# mapleCUx_large_400-012.net
KiCad netlist of a schematic drawn in EAGLE
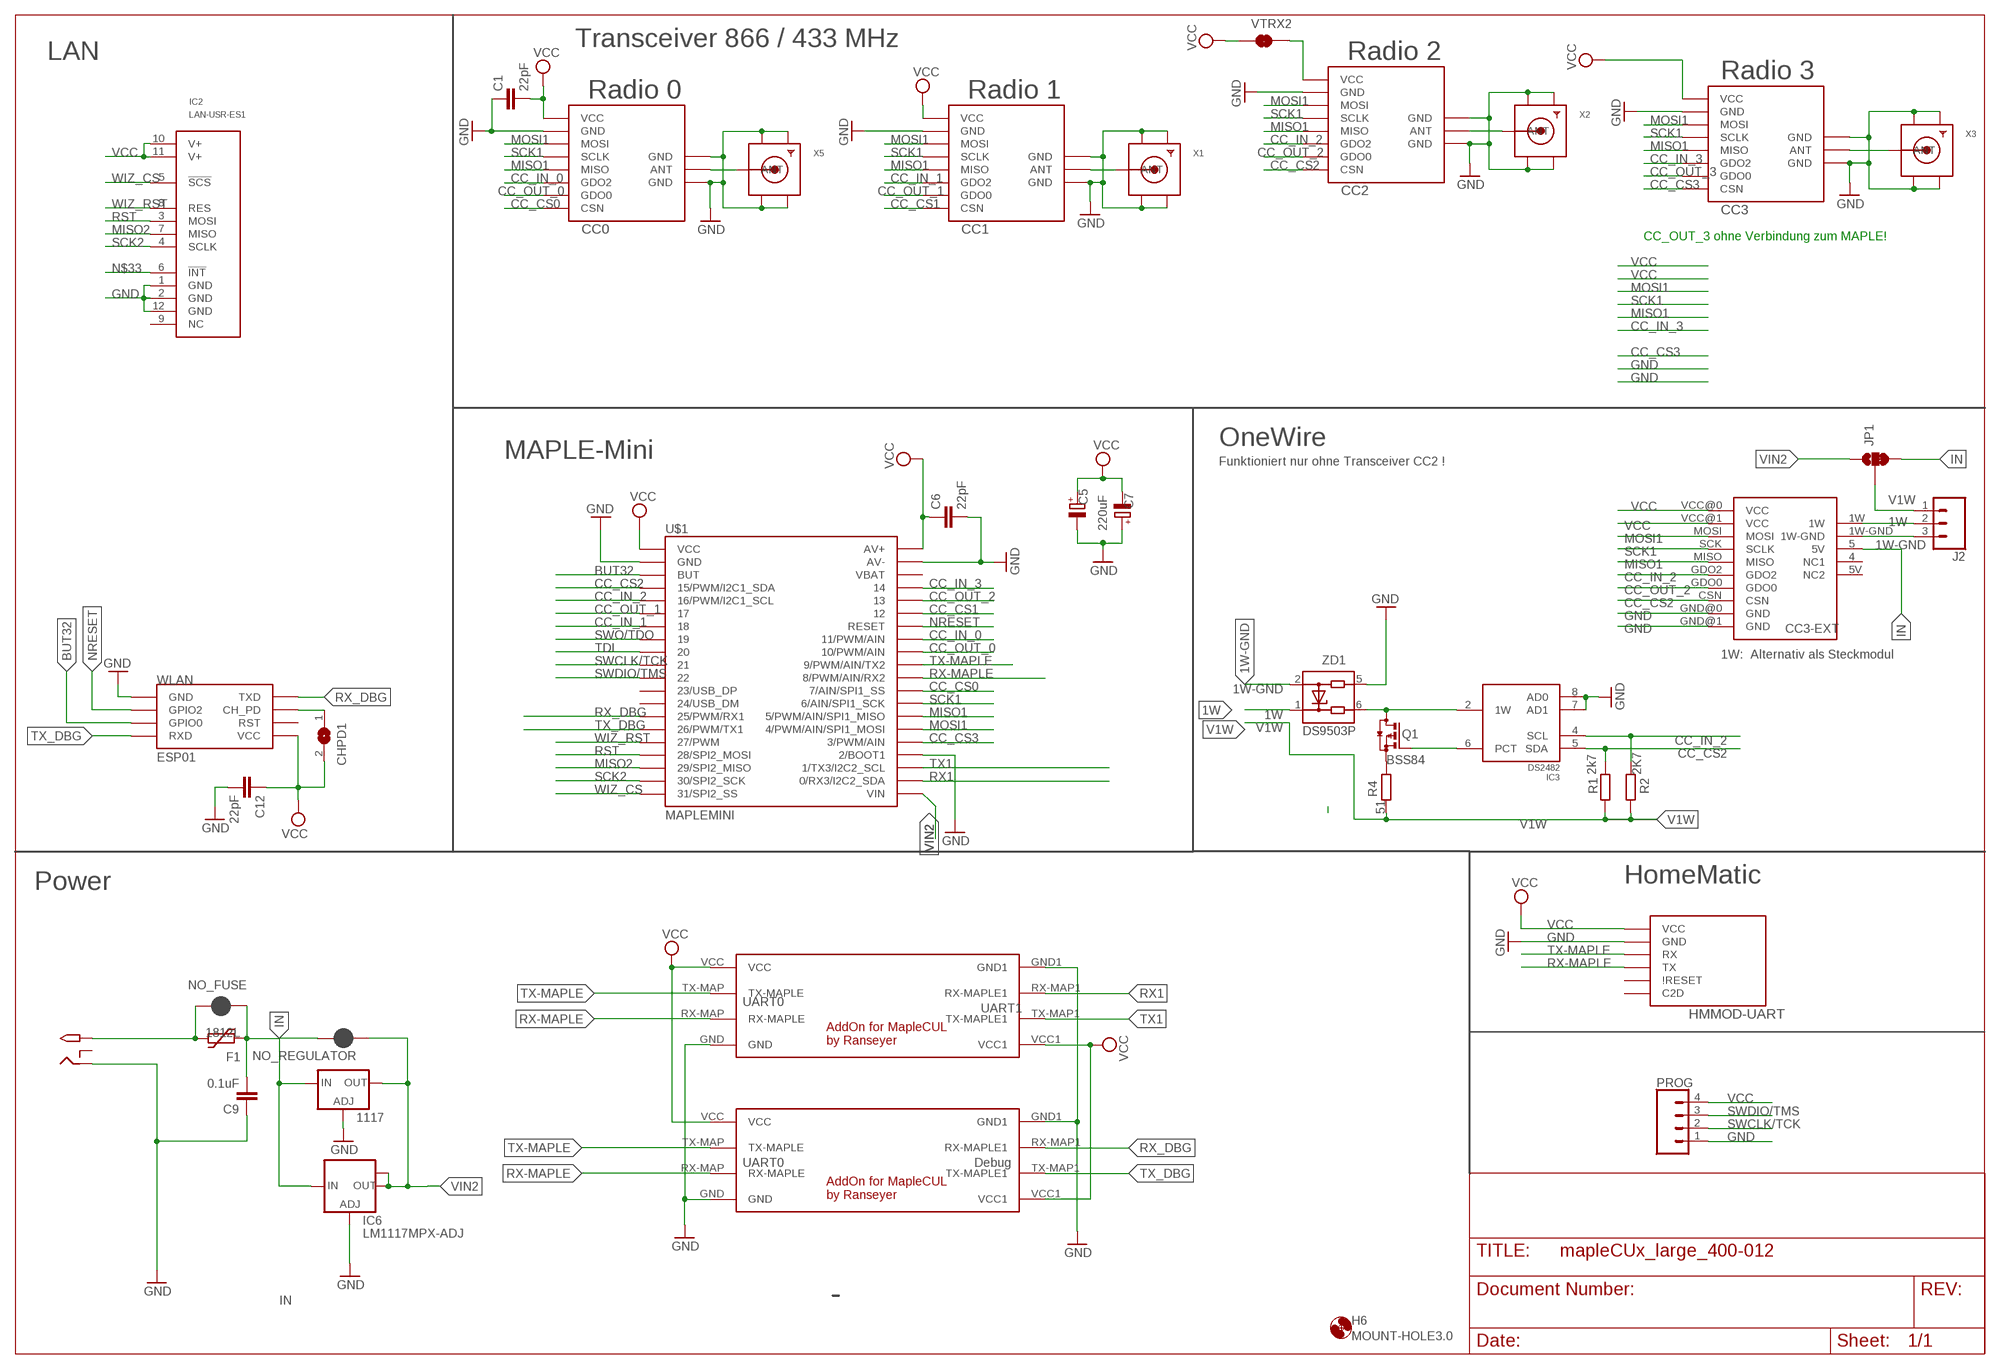
[diagram p0: schematic, sheet 1]

(export (version "E")
  (design (tool "Eeschema 10.0.6"))
  (components
    (comp (ref "1117")
      (value "LD117ADT50TR")
      (footprint "eagle-import:DPACK")
      (libsource (lib "eagle-import") (part "LD117A?DT50TR"))
    )
    (comp (ref "C1")
      (value "22pF")
      (footprint "eagle-import:C0805")
      (libsource (lib "eagle-import") (part "C-EUC0805"))
    )
    (comp (ref "C5")
      (value "220uF")
      (footprint "eagle-import:E5-8,5")
      (libsource (lib "eagle-import") (part "CPOL-EUE5-8.5"))
    )
    (comp (ref "C6")
      (value "22pF")
      (footprint "eagle-import:C0805")
      (libsource (lib "eagle-import") (part "C-EUC0805"))
    )
    (comp (ref "C7")
      (value "CPOL-EUSMCE")
      (footprint "eagle-import:SMC_E")
      (libsource (lib "eagle-import") (part "rcl_334_CPOL-EUSMCE"))
    )
    (comp (ref "C9")
      (value "0.1uF")
      (footprint "eagle-import:C1206")
      (libsource (lib "eagle-import") (part "C-EUC1206"))
    )
    (comp (ref "C12")
      (value "22pF")
      (footprint "eagle-import:C0805")
      (libsource (lib "eagle-import") (part "C-EUC0805"))
    )
    (comp (ref "CC0")
      (value "CC1101")
      (footprint "eagle-import:CC1101_MODULE1_SMD")
      (libsource (lib "eagle-import") (part "CC1101_MODULE1SMD"))
    )
    (comp (ref "CC1")
      (value "CC1101_MODULE1SMD")
      (footprint "eagle-import:CC1101_MODULE1_SMD")
      (libsource (lib "eagle-import") (part "CC1101_MODULE1SMD"))
    )
    (comp (ref "CC2")
      (value "CC1101_MODULE1SMD")
      (footprint "eagle-import:CC1101_MODULE1_SMD")
      (libsource (lib "eagle-import") (part "CC1101_MODULE1SMD"))
    )
    (comp (ref "CC3")
      (value "CC1101_MODULE1SMD")
      (footprint "eagle-import:CC1101_MODULE1_SMD")
      (libsource (lib "eagle-import") (part "CC1101_MODULE1SMD"))
    )
    (comp (ref "CC3-EXT")
      (value "ONEWIRE-MODULE")
      (footprint "eagle-import:ONEWIRE_CC1101_MODULE3_DIL")
      (libsource (lib "eagle-import") (part "ONEWIRE-MODULE"))
    )
    (comp (ref "CHPD1")
      (value "SJ")
      (footprint "eagle-import:SJ")
      (libsource (lib "eagle-import") (part "SJ"))
    )
    (comp (ref "F1")
      (value "1812L")
      (footprint "eagle-import:1812L")
      (libsource (lib "eagle-import") (part "1812L"))
    )
    (comp (ref "H6")
      (value "MOUNT-HOLE3.0")
      (footprint "eagle-import:3,0")
      (libsource (lib "eagle-import") (part "MOUNT-HOLE3.0"))
    )
    (comp (ref "HMMOD-UART")
      (value "HM-MOD-UARTDIL")
      (footprint "eagle-import:HM-MOD-UART-DIL")
      (libsource (lib "eagle-import") (part "HM-MOD-UARTDIL"))
    )
    (comp (ref "IC2")
      (value "LAN-USR-ES1")
      (footprint "eagle-import:USR-ES1")
      (libsource (lib "eagle-import") (part "LAN-USR-ES1"))
    )
    (comp (ref "IC3")
      (value "DS2482")
      (footprint "eagle-import:SO08")
      (libsource (lib "eagle-import") (part "DS2482-100S"))
    )
    (comp (ref "IC6")
      (value "LM1117MPX-ADJ")
      (footprint "eagle-import:SOT223")
      (libsource (lib "eagle-import") (part "LM1117MPX-ADJ"))
    )
    (comp (ref "J2")
      (value "CONN_03LONGPADS")
      (footprint "eagle-import:1X03_LONGPADS")
      (libsource (lib "eagle-import") (part "CONN_03LONGPADS"))
    )
    (comp (ref "JP1")
      (value "JUMPER-SMT_3_1-NC_TRACE_SILK")
      (footprint "eagle-import:SMT-JUMPER_3_1-NC_TRACE_SILK")
      (libsource (lib "eagle-import") (part "JUMPER-SMT_3_1-NC_TRACE_SILK"))
    )
    (comp (ref "NO_FUSE")
      (value "JUMPER-SMT_2_NC_PASTE_NO-SILK")
      (footprint "eagle-import:SMT-JUMPER_2_NC_PASTE_NO-SILK")
      (libsource (lib "eagle-import") (part "JUMPER-SMT_2_NC_PASTE_NO-SILK"))
    )
    (comp (ref "NO_REGULATOR")
      (value "JUMPER-SMT_2_NC_PASTE_NO-SILK")
      (footprint "eagle-import:SMT-JUMPER_2_NC_PASTE_NO-SILK")
      (libsource (lib "eagle-import") (part "JUMPER-SMT_2_NC_PASTE_NO-SILK"))
    )
    (comp (ref "PROG")
      (value "CONN_04LOCK")
      (footprint "eagle-import:1X04_LOCK")
      (libsource (lib "eagle-import") (part "CONN_04LOCK"))
    )
    (comp (ref "Q1")
      (value "BSS84")
      (footprint "eagle-import:SOT23")
      (libsource (lib "eagle-import") (part "BSS84"))
    )
    (comp (ref "R1")
      (value "2k7")
      (footprint "eagle-import:R0805")
      (libsource (lib "eagle-import") (part "R-EU_R0805"))
    )
    (comp (ref "R2")
      (value "2K7")
      (footprint "eagle-import:R0805")
      (libsource (lib "eagle-import") (part "R-EU_R0805"))
    )
    (comp (ref "R4")
      (value "51")
      (footprint "eagle-import:R0805")
      (libsource (lib "eagle-import") (part "R-EU_R0805"))
    )
    (comp (ref "U$1")
      (value "MAPLEMINI")
      (footprint "eagle-import:20-DIP")
      (libsource (lib "eagle-import") (part "MAPLEMINI"))
    )
    (comp (ref "U$2")
      (value "2.1MMJACKTHM")
      (footprint "eagle-import:PJ-102A")
      (libsource (lib "eagle-import") (part "2.1MMJACKTHM"))
    )
    (comp (ref "U$3")
      (value "MAPLE-CUL-ADDON-V01")
      (footprint "eagle-import:MAPLE-CUL-V01")
      (libsource (lib "eagle-import") (part "MAPLE-CUL-ADDON-V01"))
    )
    (comp (ref "U$4")
      (value "MAPLE-CUL-ADDON-V01")
      (footprint "eagle-import:MAPLE-CUL-V01")
      (libsource (lib "eagle-import") (part "MAPLE-CUL-ADDON-V01"))
    )
    (comp (ref "VTRX2")
      (value "JUMPER-SMT_2_NC_TRACE_SILK")
      (footprint "eagle-import:SMT-JUMPER_2_NC_TRACE_SILK")
      (libsource (lib "eagle-import") (part "JUMPER-SMT_2_NC_TRACE_SILK"))
    )
    (comp (ref "WLAN")
      (value "ESP01")
      (footprint "eagle-import:ESP01")
      (libsource (lib "eagle-import") (part "ESP01"))
    )
    (comp (ref "X1")
      (value "SMACONNECTOR_EDGE")
      (footprint "eagle-import:SMA_EDGELAUNCH")
      (libsource (lib "eagle-import") (part "SMACONNECTOR_EDGE"))
    )
    (comp (ref "X2")
      (value "SMACONNECTOR_EDGE")
      (footprint "eagle-import:SMA_EDGELAUNCH")
      (libsource (lib "eagle-import") (part "SMACONNECTOR_EDGE"))
    )
    (comp (ref "X3")
      (value "SMACONNECTOR_EDGE")
      (footprint "eagle-import:SMA_EDGELAUNCH")
      (libsource (lib "eagle-import") (part "SMACONNECTOR_EDGE"))
    )
    (comp (ref "X5")
      (value "SMACONNECTOR_EDGE")
      (footprint "eagle-import:SMA_EDGELAUNCH")
      (libsource (lib "eagle-import") (part "SMACONNECTOR_EDGE"))
    )
    (comp (ref "ZD1")
      (value "DS9503P")
      (footprint "eagle-import:TSOC6")
      (libsource (lib "eagle-import") (part "DS9503P"))
    )
  )
  (nets
    (net (code "1") (name "/CC_CS0") (class "Default")
      (node (ref "CC0") (pin "CSN") (pinfunction "CSN_CSN") (pintype "bidirectional"))
      (node (ref "U$1") (pin "29") (pinfunction "7/AIN/SPI1_SS_29") (pintype "bidirectional"))
    )
    (net (code "2") (name "/CC_CS1") (class "Default")
      (node (ref "CC1") (pin "CSN") (pinfunction "CSN_CSN") (pintype "bidirectional"))
      (node (ref "U$1") (pin "35") (pinfunction "12_35") (pintype "bidirectional"))
    )
    (net (code "3") (name "/CC_CS2") (class "Default")
      (node (ref "CC2") (pin "CSN") (pinfunction "CSN_CSN") (pintype "bidirectional"))
      (node (ref "CC3-EXT") (pin "CSN") (pinfunction "CSN_CSN") (pintype "bidirectional"))
      (node (ref "IC3") (pin "5") (pinfunction "SDA_5") (pintype "bidirectional"))
      (node (ref "R1") (pin "2") (pinfunction "2_2") (pintype "passive"))
      (node (ref "U$1") (pin "4") (pinfunction "15/PWM/I2C1_SDA_4") (pintype "bidirectional"))
    )
    (net (code "4") (name "/CC_CS3") (class "Default")
      (node (ref "CC3") (pin "CSN") (pinfunction "CSN_CSN") (pintype "bidirectional"))
      (node (ref "U$1") (pin "25") (pinfunction "3/PWM/AIN_25") (pintype "bidirectional"))
    )
    (net (code "5") (name "/CC_IN_0") (class "Default")
      (node (ref "CC0") (pin "GDO2") (pinfunction "GDO2_GDO2") (pintype "bidirectional"))
      (node (ref "U$1") (pin "33") (pinfunction "11/PWM/AIN_33") (pintype "bidirectional"))
    )
    (net (code "6") (name "/CC_IN_1") (class "Default")
      (node (ref "CC1") (pin "GDO2") (pinfunction "GDO2_GDO2") (pintype "bidirectional"))
      (node (ref "U$1") (pin "7") (pinfunction "18_7") (pintype "bidirectional"))
    )
    (net (code "7") (name "/CC_IN_2") (class "Default")
      (node (ref "CC2") (pin "GDO2") (pinfunction "GDO2_GDO2") (pintype "bidirectional"))
      (node (ref "CC3-EXT") (pin "GDO2") (pinfunction "GDO2_GDO2") (pintype "bidirectional"))
      (node (ref "IC3") (pin "4") (pinfunction "SCL_4") (pintype "input"))
      (node (ref "R2") (pin "2") (pinfunction "2_2") (pintype "passive"))
      (node (ref "U$1") (pin "5") (pinfunction "16/PWM/I2C1_SCL_5") (pintype "bidirectional"))
    )
    (net (code "8") (name "/CC_IN_3") (class "Default")
      (node (ref "CC3") (pin "GDO2") (pinfunction "GDO2_GDO2") (pintype "bidirectional"))
      (node (ref "U$1") (pin "37") (pinfunction "14_37") (pintype "bidirectional"))
    )
    (net (code "9") (name "/CC_OUT_0") (class "Default")
      (node (ref "CC0") (pin "GDO0") (pinfunction "GDO0_GDO0") (pintype "bidirectional"))
      (node (ref "U$1") (pin "32") (pinfunction "10/PWM/AIN_32") (pintype "bidirectional"))
    )
    (net (code "10") (name "/CC_OUT_1") (class "Default")
      (node (ref "CC1") (pin "GDO0") (pinfunction "GDO0_GDO0") (pintype "bidirectional"))
      (node (ref "U$1") (pin "6") (pinfunction "17_6") (pintype "bidirectional"))
    )
    (net (code "11") (name "/CC_OUT_2") (class "Default")
      (node (ref "CC2") (pin "GDO0") (pinfunction "GDO0_GDO0") (pintype "bidirectional"))
      (node (ref "CC3-EXT") (pin "GDO0") (pinfunction "GDO0_GDO0") (pintype "bidirectional"))
      (node (ref "U$1") (pin "36") (pinfunction "13_36") (pintype "bidirectional"))
    )
    (net (code "12") (name "/CC_OUT_3") (class "Default")
      (node (ref "CC3") (pin "GDO0") (pinfunction "GDO0_GDO0") (pintype "bidirectional"))
    )
    (net (code "13") (name "/MISO1") (class "Default")
      (node (ref "CC0") (pin "MISO") (pinfunction "MISO_MISO") (pintype "bidirectional"))
      (node (ref "CC1") (pin "MISO") (pinfunction "MISO_MISO") (pintype "bidirectional"))
      (node (ref "CC2") (pin "MISO") (pinfunction "MISO_MISO") (pintype "bidirectional"))
      (node (ref "CC3") (pin "MISO") (pinfunction "MISO_MISO") (pintype "bidirectional"))
      (node (ref "CC3-EXT") (pin "MISO") (pinfunction "MISO_MISO") (pintype "bidirectional"))
      (node (ref "U$1") (pin "27") (pinfunction "5/PWM/AIN/SPI1_MISO_27") (pintype "bidirectional"))
    )
    (net (code "14") (name "/MISO2") (class "Default")
      (node (ref "IC2") (pin "7") (pinfunction "MISO_7") (pintype "bidirectional"))
      (node (ref "U$1") (pin "18") (pinfunction "29/SPI2_MISO_18") (pintype "bidirectional"))
    )
    (net (code "15") (name "/MOSI1") (class "Default")
      (node (ref "CC0") (pin "MOSI") (pinfunction "MOSI_MOSI") (pintype "bidirectional"))
      (node (ref "CC1") (pin "MOSI") (pinfunction "MOSI_MOSI") (pintype "bidirectional"))
      (node (ref "CC2") (pin "MOSI") (pinfunction "MOSI_MOSI") (pintype "bidirectional"))
      (node (ref "CC3") (pin "MOSI") (pinfunction "MOSI_MOSI") (pintype "bidirectional"))
      (node (ref "CC3-EXT") (pin "MOSI") (pinfunction "MOSI_MOSI") (pintype "bidirectional"))
      (node (ref "U$1") (pin "26") (pinfunction "4/PWM/AIN/SPI1_MOSI_26") (pintype "bidirectional"))
    )
    (net (code "16") (name "/N$33") (class "Default")
      (node (ref "IC2") (pin "6") (pinfunction "~{INT}_6") (pintype "output"))
    )
    (net (code "17") (name "/RST") (class "Default")
      (node (ref "IC2") (pin "3") (pinfunction "MOSI_3") (pintype "bidirectional"))
      (node (ref "U$1") (pin "17") (pinfunction "28/SPI2_MOSI_17") (pintype "bidirectional"))
    )
    (net (code "18") (name "/SCK1") (class "Default")
      (node (ref "CC0") (pin "SCLK") (pinfunction "SCLK_SCLK") (pintype "bidirectional"))
      (node (ref "CC1") (pin "SCLK") (pinfunction "SCLK_SCLK") (pintype "bidirectional"))
      (node (ref "CC2") (pin "SCLK") (pinfunction "SCLK_SCLK") (pintype "bidirectional"))
      (node (ref "CC3") (pin "SCLK") (pinfunction "SCLK_SCLK") (pintype "bidirectional"))
      (node (ref "CC3-EXT") (pin "SCK") (pinfunction "SCLK_SCK") (pintype "bidirectional"))
      (node (ref "U$1") (pin "28") (pinfunction "6/AIN/SPI1_SCK_28") (pintype "bidirectional"))
    )
    (net (code "19") (name "/SCK2") (class "Default")
      (node (ref "IC2") (pin "4") (pinfunction "SCLK_4") (pintype "input"))
      (node (ref "U$1") (pin "19") (pinfunction "30/SPI2_SCK_19") (pintype "bidirectional"))
    )
    (net (code "20") (name "/SWCLK{slash}TCK") (class "Default")
      (node (ref "PROG") (pin "2") (pinfunction "2_2") (pintype "passive"))
      (node (ref "U$1") (pin "10") (pinfunction "21_10") (pintype "bidirectional"))
    )
    (net (code "21") (name "/SWDIO{slash}TMS") (class "Default")
      (node (ref "PROG") (pin "3") (pinfunction "3_3") (pintype "passive"))
      (node (ref "U$1") (pin "11") (pinfunction "22_11") (pintype "bidirectional"))
    )
    (net (code "22") (name "/SWO{slash}TDO") (class "Default")
      (node (ref "U$1") (pin "8") (pinfunction "19_8") (pintype "bidirectional"))
    )
    (net (code "23") (name "/TDI") (class "Default")
      (node (ref "U$1") (pin "9") (pinfunction "20_9") (pintype "bidirectional"))
    )
    (net (code "24") (name "/WIZ_CS") (class "Default")
      (node (ref "IC2") (pin "5") (pinfunction "~{SCS}_5") (pintype "input"))
      (node (ref "U$1") (pin "20") (pinfunction "31/SPI2_SS_20") (pintype "bidirectional"))
    )
    (net (code "25") (name "/WIZ_RST") (class "Default")
      (node (ref "IC2") (pin "8") (pinfunction "RES_8") (pintype "input"))
      (node (ref "U$1") (pin "16") (pinfunction "27/PWM_16") (pintype "bidirectional"))
    )
    (net (code "26") (name "1W") (class "Default")
      (node (ref "CC3-EXT") (pin "1W") (pinfunction "1W_1W") (pintype "bidirectional"))
      (node (ref "J2") (pin "2") (pinfunction "2_2") (pintype "passive"))
      (node (ref "ZD1") (pin "1") (pinfunction "P$1_1") (pintype "passive"))
    )
    (net (code "27") (name "1W-GND") (class "Default")
      (node (ref "CC3-EXT") (pin "1W-GND") (pinfunction "1W-GND_1W-GND") (pintype "bidirectional"))
      (node (ref "J2") (pin "3") (pinfunction "3_3") (pintype "passive"))
      (node (ref "ZD1") (pin "2") (pinfunction "P$2_2") (pintype "passive"))
    )
    (net (code "28") (name "BUT32") (class "Default")
      (node (ref "U$1") (pin "3") (pinfunction "BUT_3") (pintype "bidirectional"))
      (node (ref "WLAN") (pin "GPIO0") (pinfunction "GPIO0_GPIO0") (pintype "bidirectional"))
    )
    (net (code "29") (name "GND") (class "Default")
      (node (ref "1117") (pin "1") (pinfunction "ADJ_1") (pintype "input"))
      (node (ref "C1") (pin "1") (pinfunction "1_1") (pintype "passive"))
      (node (ref "C12") (pin "2") (pinfunction "2_2") (pintype "passive"))
      (node (ref "C5") (pin "-") (pinfunction "-_-") (pintype "passive"))
      (node (ref "C6") (pin "2") (pinfunction "2_2") (pintype "passive"))
      (node (ref "C7") (pin "+") (pinfunction "+_+") (pintype "passive"))
      (node (ref "C9") (pin "1") (pinfunction "1_1") (pintype "passive"))
      (node (ref "CC0") (pin "GND@0") (pinfunction "GND_GND@0") (pintype "power_in"))
      (node (ref "CC0") (pin "GND@1") (pinfunction "GND_GND@1") (pintype "power_in"))
      (node (ref "CC0") (pin "GND@2") (pinfunction "GND_GND@2") (pintype "power_in"))
      (node (ref "CC1") (pin "GND@0") (pinfunction "GND_GND@0") (pintype "power_in"))
      (node (ref "CC1") (pin "GND@1") (pinfunction "GND_GND@1") (pintype "power_in"))
      (node (ref "CC1") (pin "GND@2") (pinfunction "GND_GND@2") (pintype "power_in"))
      (node (ref "CC2") (pin "GND@0") (pinfunction "GND_GND@0") (pintype "power_in"))
      (node (ref "CC2") (pin "GND@1") (pinfunction "GND_GND@1") (pintype "power_in"))
      (node (ref "CC2") (pin "GND@2") (pinfunction "GND_GND@2") (pintype "power_in"))
      (node (ref "CC3") (pin "GND@0") (pinfunction "GND_GND@0") (pintype "power_in"))
      (node (ref "CC3") (pin "GND@1") (pinfunction "GND_GND@1") (pintype "power_in"))
      (node (ref "CC3") (pin "GND@2") (pinfunction "GND_GND@2") (pintype "power_in"))
      (node (ref "CC3-EXT") (pin "GND@0") (pinfunction "GND_GND@0") (pintype "power_in"))
      (node (ref "CC3-EXT") (pin "GND@1") (pinfunction "GND_GND@1") (pintype "power_in"))
      (node (ref "HMMOD-UART") (pin "2") (pinfunction "GND_2") (pintype "power_in"))
      (node (ref "IC2") (pin "1") (pinfunction "GND_1") (pintype "power_in"))
      (node (ref "IC2") (pin "12") (pinfunction "GND_12") (pintype "power_in"))
      (node (ref "IC2") (pin "2") (pinfunction "GND_2") (pintype "power_in"))
      (node (ref "IC3") (pin "7") (pinfunction "AD1_7") (pintype "input"))
      (node (ref "IC3") (pin "8") (pinfunction "AD0_8") (pintype "input"))
      (node (ref "IC6") (pin "1") (pinfunction "ADJ_1") (pintype "input"))
      (node (ref "PROG") (pin "1") (pinfunction "1_1") (pintype "passive"))
      (node (ref "U$1") (pin "2") (pinfunction "GND_2") (pintype "bidirectional"))
      (node (ref "U$1") (pin "24") (pinfunction "2/BOOT1_24") (pintype "bidirectional"))
      (node (ref "U$1") (pin "39") (pinfunction "AV-_39") (pintype "bidirectional"))
      (node (ref "U$2") (pin "RING") (pinfunction "RING_RING") (pintype "bidirectional"))
      (node (ref "U$3") (pin "GND") (pinfunction "GND_GND") (pintype "bidirectional"))
      (node (ref "U$3") (pin "GND1") (pinfunction "GND1_GND1") (pintype "bidirectional"))
      (node (ref "U$4") (pin "GND") (pinfunction "GND_GND") (pintype "bidirectional"))
      (node (ref "U$4") (pin "GND1") (pinfunction "GND1_GND1") (pintype "bidirectional"))
      (node (ref "WLAN") (pin "GND") (pinfunction "GND_GND") (pintype "bidirectional"))
      (node (ref "X1") (pin "GND@1") (pinfunction "GND4_GND@1") (pintype "power_in"))
      (node (ref "X1") (pin "GND@2") (pinfunction "GND3_GND@2") (pintype "power_in"))
      (node (ref "X1") (pin "GND@3") (pinfunction "GND2_GND@3") (pintype "power_in"))
      (node (ref "X1") (pin "GND@4") (pinfunction "GND1_GND@4") (pintype "power_in"))
      (node (ref "X2") (pin "GND@1") (pinfunction "GND4_GND@1") (pintype "power_in"))
      (node (ref "X2") (pin "GND@2") (pinfunction "GND3_GND@2") (pintype "power_in"))
      (node (ref "X2") (pin "GND@3") (pinfunction "GND2_GND@3") (pintype "power_in"))
      (node (ref "X2") (pin "GND@4") (pinfunction "GND1_GND@4") (pintype "power_in"))
      (node (ref "X3") (pin "GND@1") (pinfunction "GND4_GND@1") (pintype "power_in"))
      (node (ref "X3") (pin "GND@2") (pinfunction "GND3_GND@2") (pintype "power_in"))
      (node (ref "X3") (pin "GND@3") (pinfunction "GND2_GND@3") (pintype "power_in"))
      (node (ref "X3") (pin "GND@4") (pinfunction "GND1_GND@4") (pintype "power_in"))
      (node (ref "X5") (pin "GND@1") (pinfunction "GND4_GND@1") (pintype "power_in"))
      (node (ref "X5") (pin "GND@2") (pinfunction "GND3_GND@2") (pintype "power_in"))
      (node (ref "X5") (pin "GND@3") (pinfunction "GND2_GND@3") (pintype "power_in"))
      (node (ref "X5") (pin "GND@4") (pinfunction "GND1_GND@4") (pintype "power_in"))
      (node (ref "ZD1") (pin "5") (pinfunction "P$3_5") (pintype "passive"))
    )
    (net (code "30") (name "IN") (class "Default")
      (node (ref "1117") (pin "3") (pinfunction "IN_3") (pintype "input"))
      (node (ref "C9") (pin "2") (pinfunction "2_2") (pintype "passive"))
      (node (ref "CC3-EXT") (pin "5") (pinfunction "5V_5") (pintype "bidirectional"))
      (node (ref "F1") (pin "P$1") (pinfunction "1_P$1") (pintype "passive"))
      (node (ref "IC6") (pin "3") (pinfunction "IN_3") (pintype "input"))
      (node (ref "JP1") (pin "3") (pinfunction "3_3") (pintype "passive"))
      (node (ref "NO_FUSE") (pin "1") (pinfunction "1_1") (pintype "passive"))
      (node (ref "NO_REGULATOR") (pin "2") (pinfunction "2_2") (pintype "passive"))
    )
    (net (code "31") (name "NRESET") (class "Default")
      (node (ref "U$1") (pin "34") (pinfunction "RESET_34") (pintype "bidirectional"))
      (node (ref "WLAN") (pin "GPIO2") (pinfunction "GPIO2_GPIO2") (pintype "bidirectional"))
    )
    (net (code "32") (name "Net-(CC2-PadVCC)") (class "Default")
      (node (ref "CC2") (pin "VCC") (pinfunction "VCC_VCC") (pintype "power_in"))
      (node (ref "VTRX2") (pin "2") (pinfunction "2_2") (pintype "passive"))
    )
    (net (code "33") (name "Net-(CHPD1-Pad1)") (class "Default")
      (node (ref "CHPD1") (pin "1") (pinfunction "1_1") (pintype "passive"))
      (node (ref "WLAN") (pin "CH_PD") (pinfunction "CH_PD_CH_PD") (pintype "bidirectional"))
    )
    (net (code "34") (name "Net-(F1-2)") (class "Default")
      (node (ref "F1") (pin "P$2") (pinfunction "2_P$2") (pintype "passive"))
      (node (ref "NO_FUSE") (pin "2") (pinfunction "2_2") (pintype "passive"))
      (node (ref "U$2") (pin "TIP") (pinfunction "TIP_TIP") (pintype "bidirectional"))
    )
    (net (code "35") (name "Net-(IC3A-1W)") (class "Default")
      (node (ref "IC3") (pin "2") (pinfunction "1W_2") (pintype "open_collector"))
      (node (ref "Q1") (pin "3") (pinfunction "D_3") (pintype "passive"))
      (node (ref "ZD1") (pin "6") (pinfunction "P$4_6") (pintype "passive"))
    )
    (net (code "36") (name "Net-(IC3A-PCT)") (class "Default")
      (node (ref "IC3") (pin "6") (pinfunction "PCT_6") (pintype "output"))
      (node (ref "Q1") (pin "1") (pinfunction "G_1") (pintype "passive"))
    )
    (net (code "37") (name "Net-(Q1-S)") (class "Default")
      (node (ref "Q1") (pin "2") (pinfunction "S_2") (pintype "passive"))
      (node (ref "R4") (pin "1") (pinfunction "1_1") (pintype "passive"))
    )
    (net (code "38") (name "Net-(X1-ANT)") (class "Default")
      (node (ref "CC1") (pin "ANT") (pinfunction "ANT_ANT") (pintype "output"))
      (node (ref "X1") (pin "P") (pinfunction "ANT_P") (pintype "bidirectional"))
    )
    (net (code "39") (name "Net-(X2-ANT)") (class "Default")
      (node (ref "CC2") (pin "ANT") (pinfunction "ANT_ANT") (pintype "output"))
      (node (ref "X2") (pin "P") (pinfunction "ANT_P") (pintype "bidirectional"))
    )
    (net (code "40") (name "Net-(X3-ANT)") (class "Default")
      (node (ref "CC3") (pin "ANT") (pinfunction "ANT_ANT") (pintype "output"))
      (node (ref "X3") (pin "P") (pinfunction "ANT_P") (pintype "bidirectional"))
    )
    (net (code "41") (name "Net-(X5-ANT)") (class "Default")
      (node (ref "CC0") (pin "ANT") (pinfunction "ANT_ANT") (pintype "output"))
      (node (ref "X5") (pin "P") (pinfunction "ANT_P") (pintype "bidirectional"))
    )
    (net (code "42") (name "RX-MAPLE") (class "Default")
      (node (ref "HMMOD-UART") (pin "5") (pinfunction "TX_5") (pintype "bidirectional"))
      (node (ref "U$1") (pin "30") (pinfunction "8/PWM/AIN/RX2_30") (pintype "bidirectional"))
      (node (ref "U$3") (pin "RX-MAP") (pinfunction "RX-MAPLE_RX-MAP") (pintype "bidirectional"))
      (node (ref "U$4") (pin "RX-MAP") (pinfunction "RX-MAPLE_RX-MAP") (pintype "bidirectional"))
    )
    (net (code "43") (name "RX1") (class "Default")
      (node (ref "U$1") (pin "22") (pinfunction "0/RX3/I2C2_SDA_22") (pintype "bidirectional"))
      (node (ref "U$3") (pin "RX-MAP1") (pinfunction "RX-MAPLE1_RX-MAP1") (pintype "bidirectional"))
    )
    (net (code "44") (name "RX_DBG") (class "Default")
      (node (ref "U$1") (pin "14") (pinfunction "25/PWM/RX1_14") (pintype "bidirectional"))
      (node (ref "U$4") (pin "RX-MAP1") (pinfunction "RX-MAPLE1_RX-MAP1") (pintype "bidirectional"))
      (node (ref "WLAN") (pin "TX") (pinfunction "TXD_TX") (pintype "bidirectional"))
    )
    (net (code "45") (name "TX-MAPLE") (class "Default")
      (node (ref "HMMOD-UART") (pin "6") (pinfunction "RX_6") (pintype "bidirectional"))
      (node (ref "U$1") (pin "31") (pinfunction "9/PWM/AIN/TX2_31") (pintype "bidirectional"))
      (node (ref "U$3") (pin "TX-MAP") (pinfunction "TX-MAPLE_TX-MAP") (pintype "bidirectional"))
      (node (ref "U$4") (pin "TX-MAP") (pinfunction "TX-MAPLE_TX-MAP") (pintype "bidirectional"))
    )
    (net (code "46") (name "TX1") (class "Default")
      (node (ref "U$1") (pin "23") (pinfunction "1/TX3/I2C2_SCL_23") (pintype "bidirectional"))
      (node (ref "U$3") (pin "TX-MAP1") (pinfunction "TX-MAPLE1_TX-MAP1") (pintype "bidirectional"))
    )
    (net (code "47") (name "TX_DBG") (class "Default")
      (node (ref "U$1") (pin "15") (pinfunction "26/PWM/TX1_15") (pintype "bidirectional"))
      (node (ref "U$4") (pin "TX-MAP1") (pinfunction "TX-MAPLE1_TX-MAP1") (pintype "bidirectional"))
      (node (ref "WLAN") (pin "RX") (pinfunction "RXD_RX") (pintype "bidirectional"))
    )
    (net (code "48") (name "V1W") (class "Default")
      (node (ref "J2") (pin "1") (pinfunction "1_1") (pintype "passive"))
      (node (ref "JP1") (pin "2") (pinfunction "2_2") (pintype "passive"))
      (node (ref "R1") (pin "1") (pinfunction "1_1") (pintype "passive"))
      (node (ref "R2") (pin "1") (pinfunction "1_1") (pintype "passive"))
      (node (ref "R4") (pin "2") (pinfunction "2_2") (pintype "passive"))
    )
    (net (code "49") (name "VCC") (class "Default")
      (node (ref "C1") (pin "2") (pinfunction "2_2") (pintype "passive"))
      (node (ref "C12") (pin "1") (pinfunction "1_1") (pintype "passive"))
      (node (ref "C5") (pin "+") (pinfunction "+_+") (pintype "passive"))
      (node (ref "C6") (pin "1") (pinfunction "1_1") (pintype "passive"))
      (node (ref "C7") (pin "-") (pinfunction "-_-") (pintype "passive"))
      (node (ref "CC0") (pin "VCC") (pinfunction "VCC_VCC") (pintype "power_in"))
      (node (ref "CC1") (pin "VCC") (pinfunction "VCC_VCC") (pintype "power_in"))
      (node (ref "CC3") (pin "VCC") (pinfunction "VCC_VCC") (pintype "power_in"))
      (node (ref "CC3-EXT") (pin "VCC@0") (pinfunction "VCC_VCC@0") (pintype "power_in"))
      (node (ref "CC3-EXT") (pin "VCC@1") (pinfunction "VCC_VCC@1") (pintype "power_in"))
      (node (ref "CHPD1") (pin "2") (pinfunction "2_2") (pintype "passive"))
      (node (ref "HMMOD-UART") (pin "1") (pinfunction "VCC_1") (pintype "power_in"))
      (node (ref "IC2") (pin "10") (pinfunction "V+_10") (pintype "power_in"))
      (node (ref "IC2") (pin "11") (pinfunction "V+_11") (pintype "power_in"))
      (node (ref "PROG") (pin "4") (pinfunction "4_4") (pintype "passive"))
      (node (ref "U$1") (pin "1") (pinfunction "VCC_1") (pintype "bidirectional"))
      (node (ref "U$1") (pin "40") (pinfunction "AV+_40") (pintype "bidirectional"))
      (node (ref "U$3") (pin "VCC") (pinfunction "VCC_VCC") (pintype "bidirectional"))
      (node (ref "U$3") (pin "VCC1") (pinfunction "VCC1_VCC1") (pintype "bidirectional"))
      (node (ref "U$4") (pin "VCC") (pinfunction "VCC_VCC") (pintype "bidirectional"))
      (node (ref "U$4") (pin "VCC1") (pinfunction "VCC1_VCC1") (pintype "bidirectional"))
      (node (ref "VTRX2") (pin "1") (pinfunction "1_1") (pintype "passive"))
      (node (ref "WLAN") (pin "VCC") (pinfunction "VCC_VCC") (pintype "bidirectional"))
    )
    (net (code "50") (name "VIN2") (class "Default")
      (node (ref "1117") (pin "4") (pinfunction "OUT_4") (pintype "passive"))
      (node (ref "IC6") (pin "2") (pinfunction "OUT_2") (pintype "passive"))
      (node (ref "IC6") (pin "TAB") (pinfunction "OUT1_TAB") (pintype "passive"))
      (node (ref "JP1") (pin "1") (pinfunction "1_1") (pintype "passive"))
      (node (ref "NO_REGULATOR") (pin "1") (pinfunction "1_1") (pintype "passive"))
      (node (ref "U$1") (pin "21") (pinfunction "VIN_21") (pintype "bidirectional"))
    )
    (net (code "51") (name "unconnected-(CC3-EXT-NC1-Pad4)") (class "Default")
      (node (ref "CC3-EXT") (pin "4") (pinfunction "NC1_4") (pintype "bidirectional"))
    )
    (net (code "52") (name "unconnected-(CC3-EXT-NC2-Pad5V)") (class "Default")
      (node (ref "CC3-EXT") (pin "5V") (pinfunction "NC2_5V") (pintype "bidirectional"))
    )
    (net (code "53") (name "unconnected-(HMMOD-UART-C2D-Pad3)") (class "Default")
      (node (ref "HMMOD-UART") (pin "3") (pinfunction "C2D_3") (pintype "bidirectional"))
    )
    (net (code "54") (name "unconnected-(HMMOD-UART-\\~{RESET}-Pad4)") (class "Default")
      (node (ref "HMMOD-UART") (pin "4") (pinfunction "\\~{RESET}_4") (pintype "bidirectional"))
    )
    (net (code "55") (name "unconnected-(IC2-NC-Pad9)") (class "Default")
      (node (ref "IC2") (pin "9") (pinfunction "NC_9") (pintype "no_connect"))
    )
    (net (code "56") (name "unconnected-(U$1-23{slash}USB_DP-Pad12)") (class "Default")
      (node (ref "U$1") (pin "12") (pinfunction "23/USB_DP_12") (pintype "bidirectional"))
    )
    (net (code "57") (name "unconnected-(U$1-24{slash}USB_DM-Pad13)") (class "Default")
      (node (ref "U$1") (pin "13") (pinfunction "24/USB_DM_13") (pintype "bidirectional"))
    )
    (net (code "58") (name "unconnected-(U$1-VBAT-Pad38)") (class "Default")
      (node (ref "U$1") (pin "38") (pinfunction "VBAT_38") (pintype "bidirectional"))
    )
    (net (code "59") (name "unconnected-(U$2-PadRING_SW)") (class "Default")
      (node (ref "U$2") (pin "RING_SW") (pinfunction "RING_SW_RING_SW") (pintype "bidirectional"))
    )
    (net (code "60") (name "unconnected-(WLAN-PadRST)") (class "Default")
      (node (ref "WLAN") (pin "RST") (pinfunction "RST_RST") (pintype "bidirectional"))
    )
  )
)
